# carterasp_cobracasses_2_v3-1.net
KiCad netlist of a schematic drawn in EAGLE
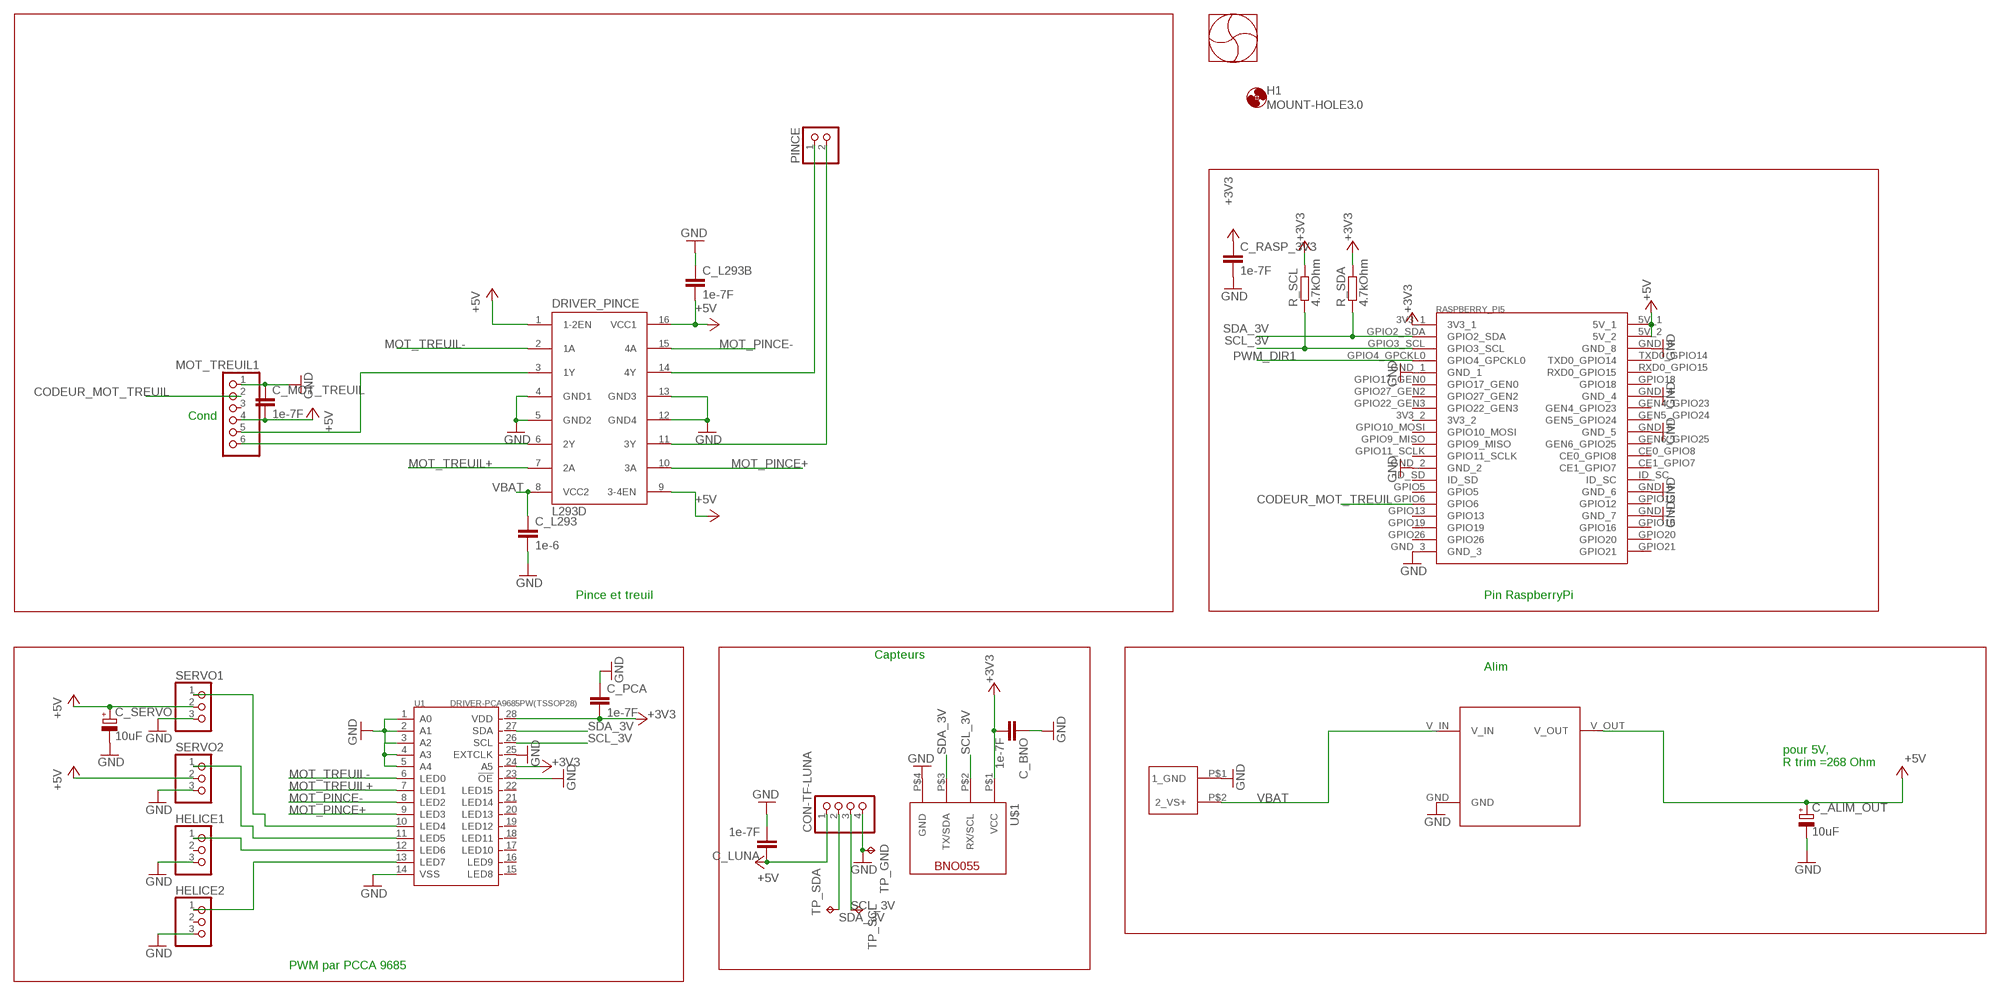
[diagram p0: schematic, sheet 1]

(export (version "E")
  (design (tool "Eeschema 10.0.6"))
  (components
    (comp (ref "CON-TF-LUNA")
      (value "PINHD-1X4")
      (footprint "eagle-import:1X04")
      (libsource (lib "eagle-import") (part "PINHD-1X4"))
    )
    (comp (ref "C_ALIM_OUT")
      (value "10uF")
      (footprint "eagle-import:E5-8,5")
      (libsource (lib "eagle-import") (part "CPOL-EUE5-8.5"))
    )
    (comp (ref "C_BNO")
      (value "1e-7F")
      (footprint "eagle-import:C1206")
      (libsource (lib "eagle-import") (part "C-EUC1206"))
    )
    (comp (ref "C_L293")
      (value "1e-6")
      (footprint "eagle-import:C1206")
      (libsource (lib "eagle-import") (part "C-EUC1206"))
    )
    (comp (ref "C_L293B")
      (value "1e-7F")
      (footprint "eagle-import:C1206")
      (libsource (lib "eagle-import") (part "C-EUC1206"))
    )
    (comp (ref "C_LUNA")
      (value "1e-7F")
      (footprint "eagle-import:C1206")
      (libsource (lib "eagle-import") (part "C-EUC1206"))
    )
    (comp (ref "C_MOT_TREUIL")
      (value "1e-7F")
      (footprint "eagle-import:C1206")
      (libsource (lib "eagle-import") (part "C-EUC1206"))
    )
    (comp (ref "C_PCA")
      (value "1e-7F")
      (footprint "eagle-import:C1206")
      (libsource (lib "eagle-import") (part "C-EUC1206"))
    )
    (comp (ref "C_RASP_3V3")
      (value "1e-7F")
      (footprint "eagle-import:C1206")
      (libsource (lib "eagle-import") (part "C-EUC1206"))
    )
    (comp (ref "C_SERVO")
      (value "10uF")
      (footprint "eagle-import:E5-8,5")
      (libsource (lib "eagle-import") (part "CPOL-EUE5-8.5"))
    )
    (comp (ref "DRIVER_PINCE")
      (value "L293D")
      (footprint "eagle-import:DIL16")
      (libsource (lib "eagle-import") (part "L293D"))
    )
    (comp (ref "H1")
      (value "MOUNT-HOLE3.0")
      (footprint "eagle-import:3,0")
      (libsource (lib "eagle-import") (part "MOUNT-HOLE3.0"))
    )
    (comp (ref "HELICE1")
      (value "PINHD-1X3")
      (footprint "eagle-import:1X03")
      (libsource (lib "eagle-import") (part "PINHD-1X3"))
    )
    (comp (ref "HELICE2")
      (value "PINHD-1X3")
      (footprint "eagle-import:1X03")
      (libsource (lib "eagle-import") (part "PINHD-1X3"))
    )
    (comp (ref "MOT_TREUIL1")
      (value "PINHD-1X6")
      (footprint "eagle-import:1X06")
      (libsource (lib "eagle-import") (part "PINHD-1X6"))
    )
    (comp (ref "PINCE")
      (value "PINHD-1X2")
      (footprint "eagle-import:1X02")
      (libsource (lib "eagle-import") (part "PINHD-1X2"))
    )
    (comp (ref "R_SCL")
      (value "4.7kOhm")
      (footprint "eagle-import:R0805")
      (libsource (lib "eagle-import") (part "R-EU_R0805"))
    )
    (comp (ref "R_SDA")
      (value "4.7kOhm")
      (footprint "eagle-import:R0805")
      (libsource (lib "eagle-import") (part "R-EU_R0805"))
    )
    (comp (ref "SERVO1")
      (value "PINHD-1X3")
      (footprint "eagle-import:1X03")
      (libsource (lib "eagle-import") (part "PINHD-1X3"))
    )
    (comp (ref "SERVO2")
      (value "PINHD-1X3")
      (footprint "eagle-import:1X03")
      (libsource (lib "eagle-import") (part "PINHD-1X3"))
    )
    (comp (ref "TP_GND")
      (value "TPPAD1-13")
      (footprint "eagle-import:P1-13")
      (libsource (lib "eagle-import") (part "TPPAD1-13"))
    )
    (comp (ref "TP_SCL")
      (value "TPPAD1-13")
      (footprint "eagle-import:P1-13")
      (libsource (lib "eagle-import") (part "TPPAD1-13"))
    )
    (comp (ref "TP_SDA")
      (value "TPPAD1-13")
      (footprint "eagle-import:P1-13")
      (libsource (lib "eagle-import") (part "TPPAD1-13"))
    )
    (comp (ref "U$1")
      (value "MODULE_BNO055")
      (footprint "eagle-import:MODULE_BNO055")
      (libsource (lib "eagle-import") (part "MODULE_BNO055"))
    )
    (comp (ref "U$2")
      (value "CONN_ALIM")
      (footprint "eagle-import:CONN_ALIM")
      (libsource (lib "eagle-import") (part "CONN_ALIM"))
    )
    (comp (ref "U$3")
      (value "RASPBERRY_PI5")
      (footprint "eagle-import:RP5")
      (libsource (lib "eagle-import") (part "RASPBERRY_PI5"))
    )
    (comp (ref "U$4")
      (value "OKL_T6_W12")
      (footprint "eagle-import:OKL_T6_W12")
      (libsource (lib "eagle-import") (part "OKL_T6_W12"))
    )
    (comp (ref "U$5")
      (value "VENTILLATEUR_RASP")
      (footprint "eagle-import:VENTILLATEUR_RASP")
      (libsource (lib "eagle-import") (part "VENTILLATEUR_RASP"))
    )
    (comp (ref "U1")
      (value "DRIVER-PCA9685PW(TSSOP28)")
      (footprint "eagle-import:TSSOP28-0.65-9.7X4.4MM")
      (fields (field (name "MF") "NXP USA") (field (name "MP") "PCA9685PW"))
      (libsource (lib "eagle-import") (part "DRIVER-PCA9685PW(TSSOP28)"))
    )
  )
  (nets
    (net (code "1") (name "+3V3") (class "Default")
      (node (ref "C_BNO") (pin "2") (pinfunction "2_2") (pintype "passive"))
      (node (ref "C_PCA") (pin "2") (pinfunction "2_2") (pintype "passive"))
      (node (ref "C_RASP_3V3") (pin "1") (pinfunction "1_1") (pintype "passive"))
      (node (ref "R_SCL") (pin "2") (pinfunction "2_2") (pintype "passive"))
      (node (ref "R_SDA") (pin "2") (pinfunction "2_2") (pintype "passive"))
      (node (ref "U$1") (pin "P$1") (pinfunction "VCC_P$1") (pintype "bidirectional"))
      (node (ref "U$3") (pin "3V3_1") (pinfunction "3V3_1_3V3_1") (pintype "bidirectional"))
      (node (ref "U1") (pin "24") (pinfunction "A5_24") (pintype "bidirectional"))
      (node (ref "U1") (pin "28") (pinfunction "VDD_28") (pintype "bidirectional"))
    )
    (net (code "2") (name "+5V") (class "Default")
      (node (ref "CON-TF-LUNA") (pin "1") (pinfunction "1_1") (pintype "passive"))
      (node (ref "C_ALIM_OUT") (pin "+") (pinfunction "+_+") (pintype "passive"))
      (node (ref "C_L293B") (pin "2") (pinfunction "2_2") (pintype "passive"))
      (node (ref "C_LUNA") (pin "1") (pinfunction "1_1") (pintype "passive"))
      (node (ref "C_MOT_TREUIL") (pin "2") (pinfunction "2_2") (pintype "passive"))
      (node (ref "C_SERVO") (pin "+") (pinfunction "+_+") (pintype "passive"))
      (node (ref "DRIVER_PINCE") (pin "1") (pinfunction "1-2EN_1") (pintype "input"))
      (node (ref "DRIVER_PINCE") (pin "16") (pinfunction "VCC1_16") (pintype "power_in"))
      (node (ref "DRIVER_PINCE") (pin "9") (pinfunction "3-4EN_9") (pintype "input"))
      (node (ref "MOT_TREUIL1") (pin "4") (pinfunction "4_4") (pintype "passive"))
      (node (ref "SERVO1") (pin "2") (pinfunction "2_2") (pintype "passive"))
      (node (ref "SERVO2") (pin "2") (pinfunction "2_2") (pintype "passive"))
      (node (ref "U$3") (pin "5V_1") (pinfunction "5V_1_5V_1") (pintype "bidirectional"))
      (node (ref "U$3") (pin "5V_2") (pinfunction "5V_2_5V_2") (pintype "bidirectional"))
      (node (ref "U$4") (pin "V_OUT") (pinfunction "V_OUT_V_OUT") (pintype "bidirectional"))
    )
    (net (code "3") (name "/CODEUR_MOT_TREUIL") (class "Default")
      (node (ref "MOT_TREUIL1") (pin "2") (pinfunction "2_2") (pintype "passive"))
      (node (ref "U$3") (pin "GPIO6") (pinfunction "GPIO6_GPIO6") (pintype "bidirectional"))
    )
    (net (code "4") (name "/MOT_PINCE+") (class "Default")
      (node (ref "DRIVER_PINCE") (pin "10") (pinfunction "3A_10") (pintype "input"))
      (node (ref "U1") (pin "9") (pinfunction "LED3_9") (pintype "bidirectional"))
    )
    (net (code "5") (name "/MOT_PINCE-") (class "Default")
      (node (ref "DRIVER_PINCE") (pin "15") (pinfunction "4A_15") (pintype "input"))
      (node (ref "U1") (pin "8") (pinfunction "LED2_8") (pintype "bidirectional"))
    )
    (net (code "6") (name "/MOT_TREUIL+") (class "Default")
      (node (ref "DRIVER_PINCE") (pin "7") (pinfunction "2A_7") (pintype "input"))
      (node (ref "U1") (pin "7") (pinfunction "LED1_7") (pintype "bidirectional"))
    )
    (net (code "7") (name "/MOT_TREUIL-") (class "Default")
      (node (ref "DRIVER_PINCE") (pin "2") (pinfunction "1A_2") (pintype "input"))
      (node (ref "U1") (pin "6") (pinfunction "LED0_6") (pintype "bidirectional"))
    )
    (net (code "8") (name "/PWM_DIR1") (class "Default")
      (node (ref "U$3") (pin "GPIO4_GPCKL0") (pinfunction "GPIO4_GPCKL0_GPIO4_GPCKL0") (pintype "bidirectional"))
    )
    (net (code "9") (name "/SCL_3V") (class "Default")
      (node (ref "CON-TF-LUNA") (pin "3") (pinfunction "3_3") (pintype "passive"))
      (node (ref "R_SCL") (pin "1") (pinfunction "1_1") (pintype "passive"))
      (node (ref "TP_SCL") (pin "TP") (pinfunction "TP_TP") (pintype "input"))
      (node (ref "U$1") (pin "P$2") (pinfunction "RX/SCL_P$2") (pintype "bidirectional"))
      (node (ref "U$3") (pin "GPIO3_SCL") (pinfunction "GPIO3_SCL_GPIO3_SCL") (pintype "bidirectional"))
      (node (ref "U1") (pin "26") (pinfunction "SCL_26") (pintype "bidirectional"))
    )
    (net (code "10") (name "/SDA_3V") (class "Default")
      (node (ref "CON-TF-LUNA") (pin "2") (pinfunction "2_2") (pintype "passive"))
      (node (ref "R_SDA") (pin "1") (pinfunction "1_1") (pintype "passive"))
      (node (ref "TP_SDA") (pin "TP") (pinfunction "TP_TP") (pintype "input"))
      (node (ref "U$1") (pin "P$3") (pinfunction "TX/SDA_P$3") (pintype "bidirectional"))
      (node (ref "U$3") (pin "GPIO2_SDA") (pinfunction "GPIO2_SDA_GPIO2_SDA") (pintype "bidirectional"))
      (node (ref "U1") (pin "27") (pinfunction "SDA_27") (pintype "bidirectional"))
    )
    (net (code "11") (name "/VBAT") (class "Default")
      (node (ref "C_L293") (pin "1") (pinfunction "1_1") (pintype "passive"))
      (node (ref "DRIVER_PINCE") (pin "8") (pinfunction "VCC2_8") (pintype "power_in"))
      (node (ref "U$2") (pin "P$2") (pinfunction "2_VS+_P$2") (pintype "bidirectional"))
      (node (ref "U$4") (pin "V_IN") (pinfunction "V_IN_V_IN") (pintype "bidirectional"))
    )
    (net (code "12") (name "GND") (class "Default")
      (node (ref "CON-TF-LUNA") (pin "4") (pinfunction "4_4") (pintype "passive"))
      (node (ref "C_ALIM_OUT") (pin "-") (pinfunction "-_-") (pintype "passive"))
      (node (ref "C_BNO") (pin "1") (pinfunction "1_1") (pintype "passive"))
      (node (ref "C_L293") (pin "2") (pinfunction "2_2") (pintype "passive"))
      (node (ref "C_L293B") (pin "1") (pinfunction "1_1") (pintype "passive"))
      (node (ref "C_LUNA") (pin "2") (pinfunction "2_2") (pintype "passive"))
      (node (ref "C_MOT_TREUIL") (pin "1") (pinfunction "1_1") (pintype "passive"))
      (node (ref "C_PCA") (pin "1") (pinfunction "1_1") (pintype "passive"))
      (node (ref "C_RASP_3V3") (pin "2") (pinfunction "2_2") (pintype "passive"))
      (node (ref "C_SERVO") (pin "-") (pinfunction "-_-") (pintype "passive"))
      (node (ref "DRIVER_PINCE") (pin "12") (pinfunction "GND4_12") (pintype "power_in"))
      (node (ref "DRIVER_PINCE") (pin "13") (pinfunction "GND3_13") (pintype "power_in"))
      (node (ref "DRIVER_PINCE") (pin "4") (pinfunction "GND1_4") (pintype "power_in"))
      (node (ref "DRIVER_PINCE") (pin "5") (pinfunction "GND2_5") (pintype "power_in"))
      (node (ref "HELICE1") (pin "3") (pinfunction "3_3") (pintype "passive"))
      (node (ref "HELICE2") (pin "3") (pinfunction "3_3") (pintype "passive"))
      (node (ref "MOT_TREUIL1") (pin "1") (pinfunction "1_1") (pintype "passive"))
      (node (ref "SERVO1") (pin "3") (pinfunction "3_3") (pintype "passive"))
      (node (ref "SERVO2") (pin "3") (pinfunction "3_3") (pintype "passive"))
      (node (ref "TP_GND") (pin "TP") (pinfunction "TP_TP") (pintype "input"))
      (node (ref "U$1") (pin "P$4") (pinfunction "GND_P$4") (pintype "bidirectional"))
      (node (ref "U$2") (pin "P$1") (pinfunction "1_GND_P$1") (pintype "bidirectional"))
      (node (ref "U$3") (pin "GND_1") (pinfunction "GND_1_GND_1") (pintype "bidirectional"))
      (node (ref "U$3") (pin "GND_2") (pinfunction "GND_2_GND_2") (pintype "bidirectional"))
      (node (ref "U$3") (pin "GND_3") (pinfunction "GND_3_GND_3") (pintype "bidirectional"))
      (node (ref "U$3") (pin "GND_4") (pinfunction "GND_4_GND_4") (pintype "bidirectional"))
      (node (ref "U$3") (pin "GND_5") (pinfunction "GND_5_GND_5") (pintype "bidirectional"))
      (node (ref "U$3") (pin "GND_6") (pinfunction "GND_6_GND_6") (pintype "bidirectional"))
      (node (ref "U$3") (pin "GND_7") (pinfunction "GND_7_GND_7") (pintype "bidirectional"))
      (node (ref "U$3") (pin "GND_8") (pinfunction "GND_8_GND_8") (pintype "bidirectional"))
      (node (ref "U$4") (pin "GND") (pinfunction "GND_GND") (pintype "bidirectional"))
      (node (ref "U1") (pin "1") (pinfunction "A0_1") (pintype "bidirectional"))
      (node (ref "U1") (pin "14") (pinfunction "VSS_14") (pintype "bidirectional"))
      (node (ref "U1") (pin "2") (pinfunction "A1_2") (pintype "bidirectional"))
      (node (ref "U1") (pin "23") (pinfunction "~{OE}_23") (pintype "bidirectional"))
      (node (ref "U1") (pin "25") (pinfunction "EXTCLK_25") (pintype "bidirectional"))
      (node (ref "U1") (pin "3") (pinfunction "A2_3") (pintype "bidirectional"))
      (node (ref "U1") (pin "4") (pinfunction "A3_4") (pintype "bidirectional"))
      (node (ref "U1") (pin "5") (pinfunction "A4_5") (pintype "bidirectional"))
    )
    (net (code "13") (name "Net-(DRIVER_PINCE-1Y)") (class "Default")
      (node (ref "DRIVER_PINCE") (pin "3") (pinfunction "1Y_3") (pintype "output"))
      (node (ref "MOT_TREUIL1") (pin "5") (pinfunction "5_5") (pintype "passive"))
    )
    (net (code "14") (name "Net-(DRIVER_PINCE-2Y)") (class "Default")
      (node (ref "DRIVER_PINCE") (pin "6") (pinfunction "2Y_6") (pintype "output"))
      (node (ref "MOT_TREUIL1") (pin "6") (pinfunction "6_6") (pintype "passive"))
    )
    (net (code "15") (name "Net-(DRIVER_PINCE-3Y)") (class "Default")
      (node (ref "DRIVER_PINCE") (pin "11") (pinfunction "3Y_11") (pintype "output"))
      (node (ref "PINCE") (pin "2") (pinfunction "2_2") (pintype "passive"))
    )
    (net (code "16") (name "Net-(DRIVER_PINCE-4Y)") (class "Default")
      (node (ref "DRIVER_PINCE") (pin "14") (pinfunction "4Y_14") (pintype "output"))
      (node (ref "PINCE") (pin "1") (pinfunction "1_1") (pintype "passive"))
    )
    (net (code "17") (name "Net-(U1-LED4)") (class "Default")
      (node (ref "SERVO1") (pin "1") (pinfunction "1_1") (pintype "passive"))
      (node (ref "U1") (pin "10") (pinfunction "LED4_10") (pintype "bidirectional"))
    )
    (net (code "18") (name "Net-(U1-LED5)") (class "Default")
      (node (ref "SERVO2") (pin "1") (pinfunction "1_1") (pintype "passive"))
      (node (ref "U1") (pin "11") (pinfunction "LED5_11") (pintype "bidirectional"))
    )
    (net (code "19") (name "Net-(U1-LED6)") (class "Default")
      (node (ref "HELICE1") (pin "1") (pinfunction "1_1") (pintype "passive"))
      (node (ref "U1") (pin "12") (pinfunction "LED6_12") (pintype "bidirectional"))
    )
    (net (code "20") (name "Net-(U1-LED7)") (class "Default")
      (node (ref "HELICE2") (pin "1") (pinfunction "1_1") (pintype "passive"))
      (node (ref "U1") (pin "13") (pinfunction "LED7_13") (pintype "bidirectional"))
    )
    (net (code "21") (name "unconnected-(HELICE1-Pad2)") (class "Default")
      (node (ref "HELICE1") (pin "2") (pinfunction "2_2") (pintype "passive"))
    )
    (net (code "22") (name "unconnected-(HELICE2-Pad2)") (class "Default")
      (node (ref "HELICE2") (pin "2") (pinfunction "2_2") (pintype "passive"))
    )
    (net (code "23") (name "unconnected-(MOT_TREUIL1-Pad3)") (class "Default")
      (node (ref "MOT_TREUIL1") (pin "3") (pinfunction "3_3") (pintype "passive"))
    )
    (net (code "24") (name "unconnected-(U$3-Pad3V3_2)") (class "Default")
      (node (ref "U$3") (pin "3V3_2") (pinfunction "3V3_2_3V3_2") (pintype "bidirectional"))
    )
    (net (code "25") (name "unconnected-(U$3-PadCE0_GPIO8)") (class "Default")
      (node (ref "U$3") (pin "CE0_GPIO8") (pinfunction "CE0_GPIO8_CE0_GPIO8") (pintype "bidirectional"))
    )
    (net (code "26") (name "unconnected-(U$3-PadCE1_GPIO7)") (class "Default")
      (node (ref "U$3") (pin "CE1_GPIO7") (pinfunction "CE1_GPIO7_CE1_GPIO7") (pintype "bidirectional"))
    )
    (net (code "27") (name "unconnected-(U$3-PadGEN4_GPIO23)") (class "Default")
      (node (ref "U$3") (pin "GEN4_GPIO23") (pinfunction "GEN4_GPIO23_GEN4_GPIO23") (pintype "bidirectional"))
    )
    (net (code "28") (name "unconnected-(U$3-PadGEN5_GPIO24)") (class "Default")
      (node (ref "U$3") (pin "GEN5_GPIO24") (pinfunction "GEN5_GPIO24_GEN5_GPIO24") (pintype "bidirectional"))
    )
    (net (code "29") (name "unconnected-(U$3-PadGEN6_GPIO25)") (class "Default")
      (node (ref "U$3") (pin "GEN6_GPIO25") (pinfunction "GEN6_GPIO25_GEN6_GPIO25") (pintype "bidirectional"))
    )
    (net (code "30") (name "unconnected-(U$3-PadGPIO5)") (class "Default")
      (node (ref "U$3") (pin "GPIO5") (pinfunction "GPIO5_GPIO5") (pintype "bidirectional"))
    )
    (net (code "31") (name "unconnected-(U$3-PadGPIO9_MISO)") (class "Default")
      (node (ref "U$3") (pin "GPIO9_MISO") (pinfunction "GPIO9_MISO_GPIO9_MISO") (pintype "bidirectional"))
    )
    (net (code "32") (name "unconnected-(U$3-PadGPIO10_MOSI)") (class "Default")
      (node (ref "U$3") (pin "GPIO10_MOSI") (pinfunction "GPIO10_MOSI_GPIO10_MOSI") (pintype "bidirectional"))
    )
    (net (code "33") (name "unconnected-(U$3-PadGPIO11_SCLK)") (class "Default")
      (node (ref "U$3") (pin "GPIO11_SCLK") (pinfunction "GPIO11_SCLK_GPIO11_SCLK") (pintype "bidirectional"))
    )
    (net (code "34") (name "unconnected-(U$3-PadGPIO12)") (class "Default")
      (node (ref "U$3") (pin "GPIO12") (pinfunction "GPIO12_GPIO12") (pintype "bidirectional"))
    )
    (net (code "35") (name "unconnected-(U$3-PadGPIO13)") (class "Default")
      (node (ref "U$3") (pin "GPIO13") (pinfunction "GPIO13_GPIO13") (pintype "bidirectional"))
    )
    (net (code "36") (name "unconnected-(U$3-PadGPIO16)") (class "Default")
      (node (ref "U$3") (pin "GPIO16") (pinfunction "GPIO16_GPIO16") (pintype "bidirectional"))
    )
    (net (code "37") (name "unconnected-(U$3-PadGPIO17_GEN0)") (class "Default")
      (node (ref "U$3") (pin "GPIO17_GEN0") (pinfunction "GPIO17_GEN0_GPIO17_GEN0") (pintype "bidirectional"))
    )
    (net (code "38") (name "unconnected-(U$3-PadGPIO18)") (class "Default")
      (node (ref "U$3") (pin "GPIO18") (pinfunction "GPIO18_GPIO18") (pintype "bidirectional"))
    )
    (net (code "39") (name "unconnected-(U$3-PadGPIO19)") (class "Default")
      (node (ref "U$3") (pin "GPIO19") (pinfunction "GPIO19_GPIO19") (pintype "bidirectional"))
    )
    (net (code "40") (name "unconnected-(U$3-PadGPIO20)") (class "Default")
      (node (ref "U$3") (pin "GPIO20") (pinfunction "GPIO20_GPIO20") (pintype "bidirectional"))
    )
    (net (code "41") (name "unconnected-(U$3-PadGPIO21)") (class "Default")
      (node (ref "U$3") (pin "GPIO21") (pinfunction "GPIO21_GPIO21") (pintype "bidirectional"))
    )
    (net (code "42") (name "unconnected-(U$3-PadGPIO22_GEN3)") (class "Default")
      (node (ref "U$3") (pin "GPIO22_GEN3") (pinfunction "GPIO22_GEN3_GPIO22_GEN3") (pintype "bidirectional"))
    )
    (net (code "43") (name "unconnected-(U$3-PadGPIO26)") (class "Default")
      (node (ref "U$3") (pin "GPIO26") (pinfunction "GPIO26_GPIO26") (pintype "bidirectional"))
    )
    (net (code "44") (name "unconnected-(U$3-PadGPIO27_GEN2)") (class "Default")
      (node (ref "U$3") (pin "GPIO27_GEN2") (pinfunction "GPIO27_GEN2_GPIO27_GEN2") (pintype "bidirectional"))
    )
    (net (code "45") (name "unconnected-(U$3-PadID_SC)") (class "Default")
      (node (ref "U$3") (pin "ID_SC") (pinfunction "ID_SC_ID_SC") (pintype "bidirectional"))
    )
    (net (code "46") (name "unconnected-(U$3-PadID_SD)") (class "Default")
      (node (ref "U$3") (pin "ID_SD") (pinfunction "ID_SD_ID_SD") (pintype "bidirectional"))
    )
    (net (code "47") (name "unconnected-(U$3-PadRXD0_GPIO15)") (class "Default")
      (node (ref "U$3") (pin "RXD0_GPIO15") (pinfunction "RXD0_GPIO15_RXD0_GPIO15") (pintype "bidirectional"))
    )
    (net (code "48") (name "unconnected-(U$3-PadTXD0_GPIO14)") (class "Default")
      (node (ref "U$3") (pin "TXD0_GPIO14") (pinfunction "TXD0_GPIO14_TXD0_GPIO14") (pintype "bidirectional"))
    )
    (net (code "49") (name "unconnected-(U1-LED8-Pad15)") (class "Default")
      (node (ref "U1") (pin "15") (pinfunction "LED8_15") (pintype "bidirectional"))
    )
    (net (code "50") (name "unconnected-(U1-LED9-Pad16)") (class "Default")
      (node (ref "U1") (pin "16") (pinfunction "LED9_16") (pintype "bidirectional"))
    )
    (net (code "51") (name "unconnected-(U1-LED10-Pad17)") (class "Default")
      (node (ref "U1") (pin "17") (pinfunction "LED10_17") (pintype "bidirectional"))
    )
    (net (code "52") (name "unconnected-(U1-LED11-Pad18)") (class "Default")
      (node (ref "U1") (pin "18") (pinfunction "LED11_18") (pintype "bidirectional"))
    )
    (net (code "53") (name "unconnected-(U1-LED12-Pad19)") (class "Default")
      (node (ref "U1") (pin "19") (pinfunction "LED12_19") (pintype "bidirectional"))
    )
    (net (code "54") (name "unconnected-(U1-LED13-Pad20)") (class "Default")
      (node (ref "U1") (pin "20") (pinfunction "LED13_20") (pintype "bidirectional"))
    )
    (net (code "55") (name "unconnected-(U1-LED14-Pad21)") (class "Default")
      (node (ref "U1") (pin "21") (pinfunction "LED14_21") (pintype "bidirectional"))
    )
    (net (code "56") (name "unconnected-(U1-LED15-Pad22)") (class "Default")
      (node (ref "U1") (pin "22") (pinfunction "LED15_22") (pintype "bidirectional"))
    )
  )
)
